# ProPrj_Attiny1616_Devboard_2024-11-25.net
KiCad netlist of a schematic drawn in EasyEDA Pro
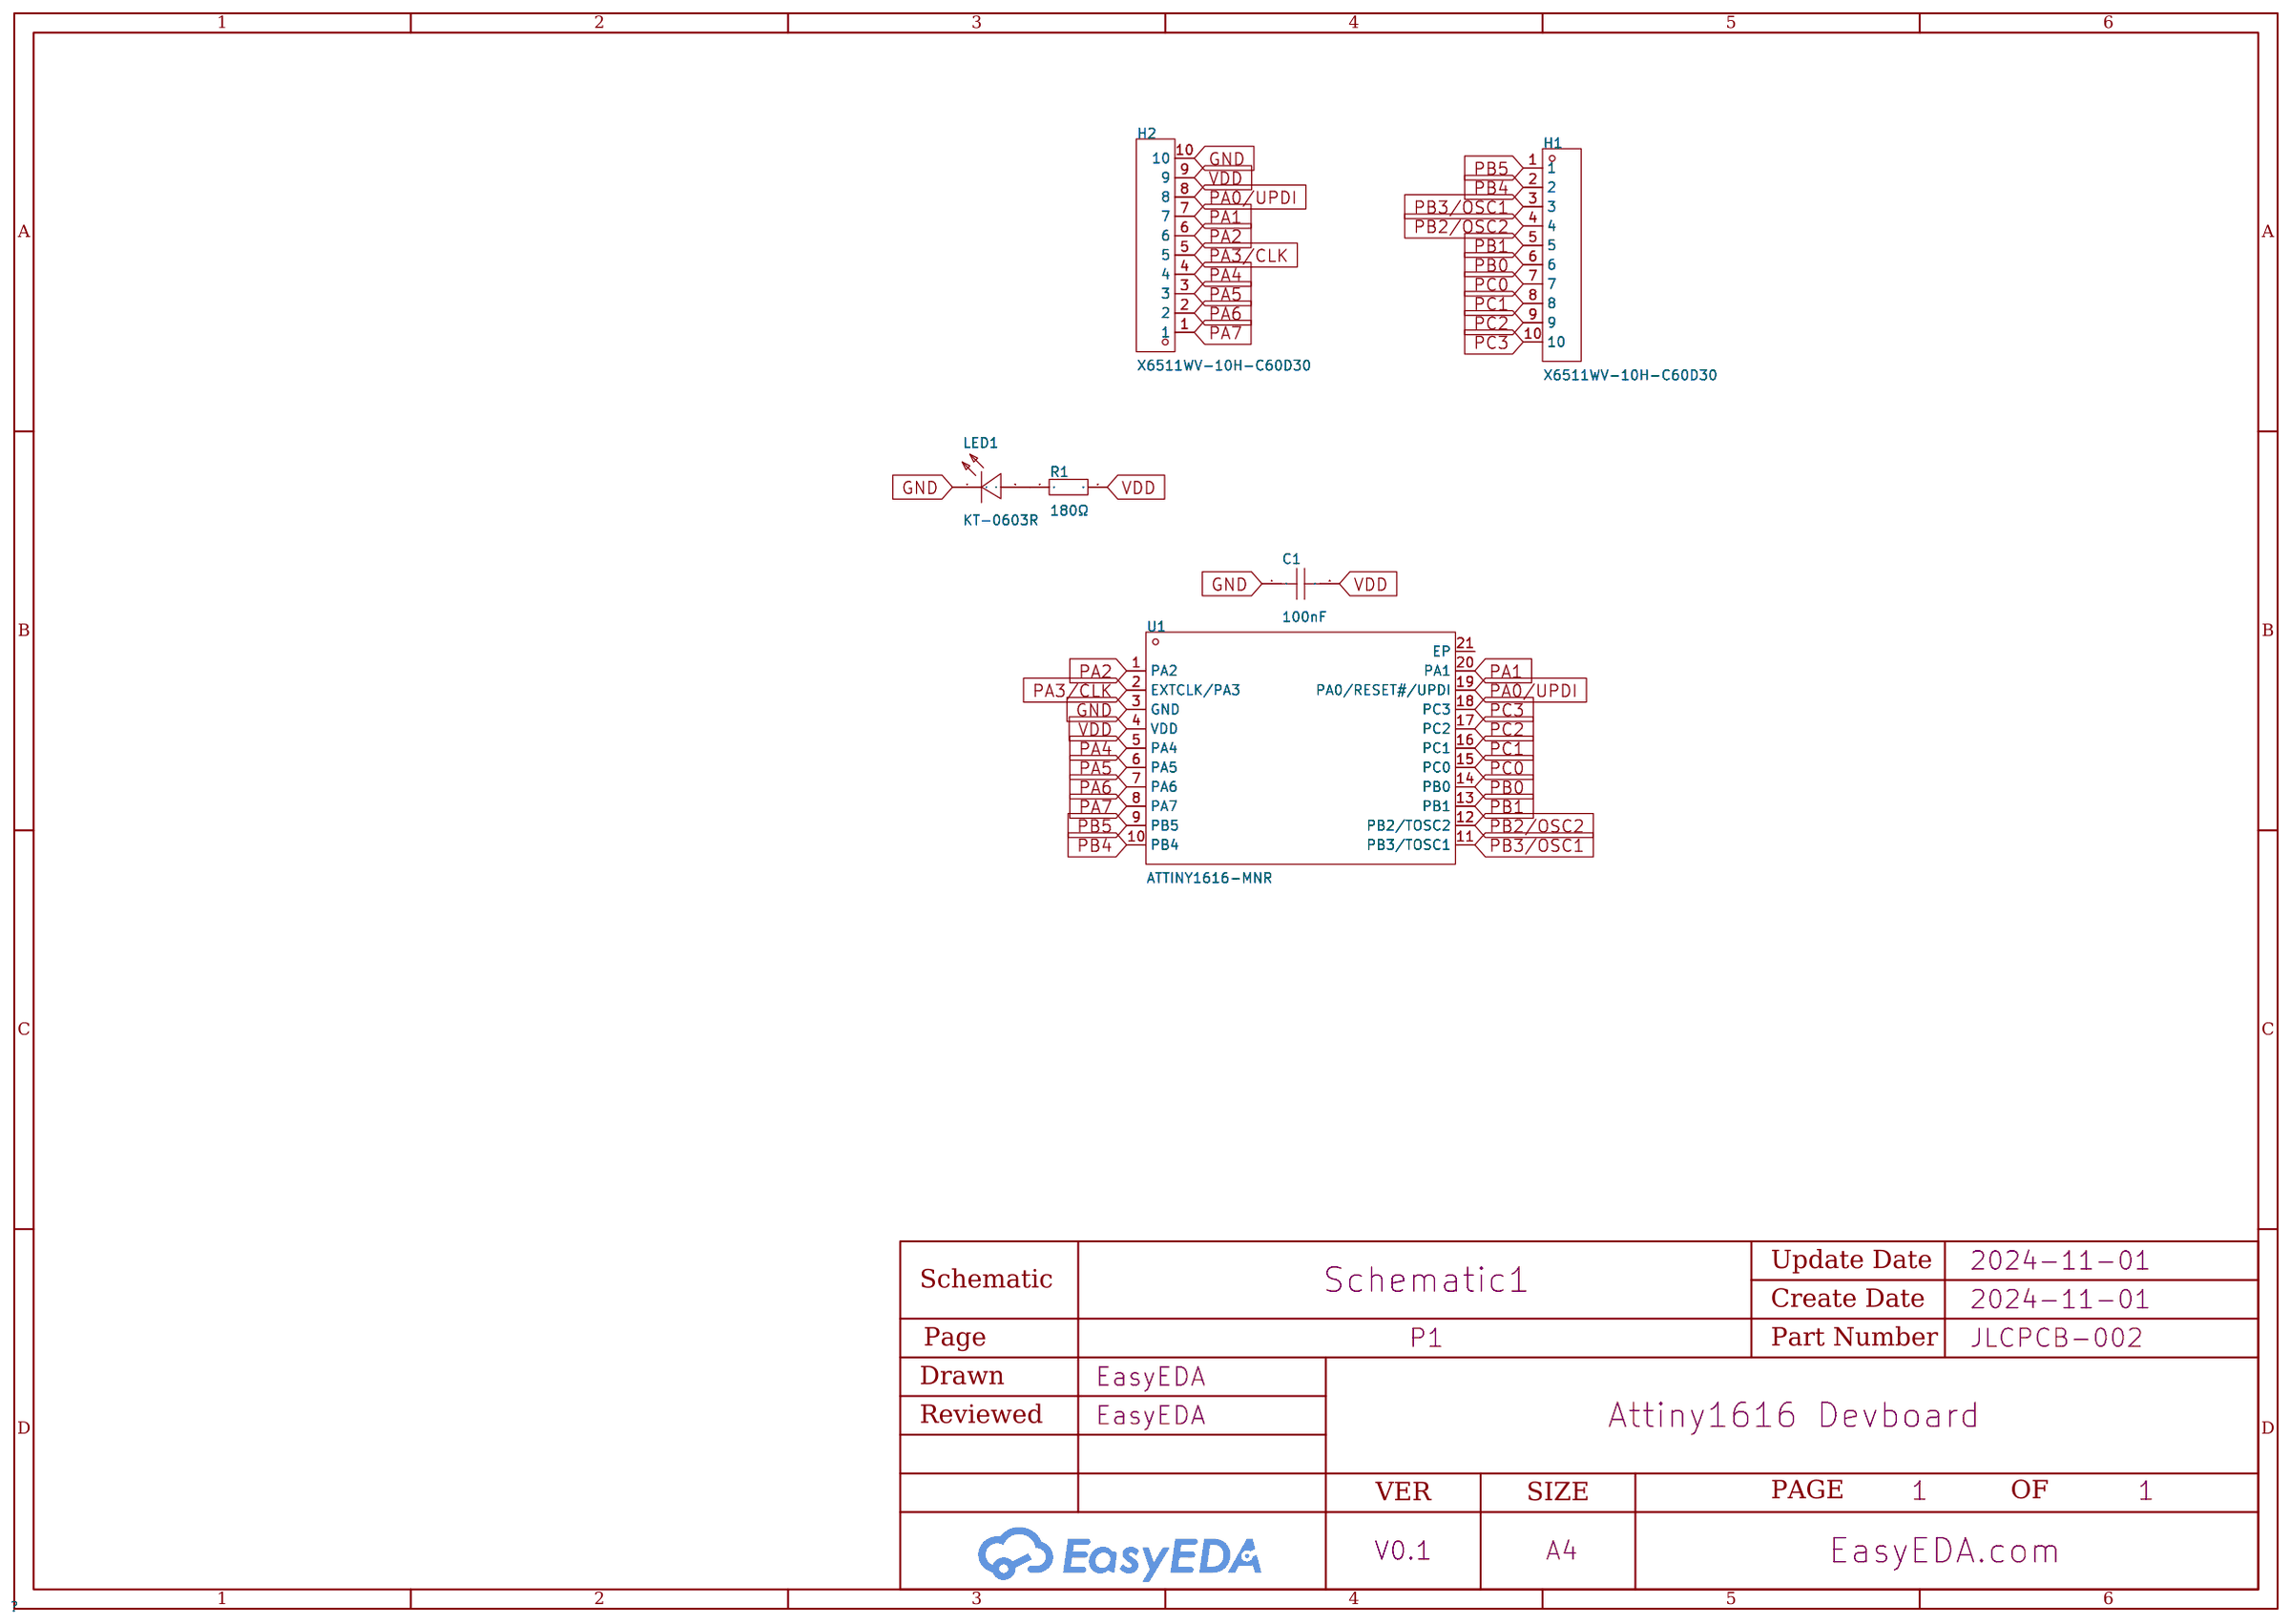
[diagram p0: schematic sheet]

(export (version "E")
  (design (tool "Eeschema 10.0.6"))
  (components
    (comp (ref "C1")
      (value "100nF")
      (footprint "easyedapro:C0402")
      (fields
        (field (name "Manufacturer Part") "CL05B104KO5NNNC")
        (field (name "Manufacturer") "SAMSUNG(三星)")
      )
      (libsource (lib "easyedapro") (part "CL05B104KO5NNNC"))
    )
    (comp (ref "H1")
      (value "X6511WV-10H-C60D30")
      (footprint "easyedapro:HDR-TH_10P-P2.54-V-M")
      (fields (field (name "Manufacturer") "XKB Connection(中国星坤)"))
      (libsource (lib "easyedapro") (part "X6511WV-10H-C30D60"))
    )
    (comp (ref "H2")
      (value "X6511WV-10H-C60D30")
      (footprint "easyedapro:HDR-TH_10P-P2.54-V-M")
      (fields (field (name "Manufacturer") "XKB Connection(中国星坤)"))
      (libsource (lib "easyedapro") (part "X6511WV-10H-C30D60"))
    )
    (comp (ref "LED1")
      (value "KT-0603R")
      (footprint "easyedapro:LED0603-RD")
      (fields (field (name "Manufacturer") "KENTO"))
      (libsource (lib "easyedapro") (part "KT-0603R"))
    )
    (comp (ref "R1")
      (value "180Ω")
      (footprint "easyedapro:R0603")
      (fields (field (name "Manufacturer Part") "RC0603FR-07180RL") (field (name "Manufacturer") "YAGEO(国巨)"))
      (libsource (lib "easyedapro") (part "RC0603FR-07180RL"))
    )
    (comp (ref "U1")
      (value "ATTINY1616-MNR")
      (footprint "easyedapro:QFN-20_L3.0-W3.0-P0.40-BL-EP1.7")
      (fields (field (name "Manufacturer") "MICROCHIP(美国微芯)"))
      (libsource (lib "easyedapro") (part "ATTINY1616-MNR"))
    )
  )
  (nets
    (net (code "1") (name "GND") (class "Default")
      (node (ref "C1") (pin "1") (pinfunction "1_1") (pintype "unspecified"))
      (node (ref "H2") (pin "10") (pinfunction "10_10") (pintype "unspecified"))
      (node (ref "LED1") (pin "1") (pinfunction "K_1") (pintype "unspecified"))
      (node (ref "U1") (pin "3") (pinfunction "GND_3") (pintype "input"))
    )
    (net (code "2") (name "Net-(LED1-A)") (class "Default")
      (node (ref "LED1") (pin "2") (pinfunction "A_2") (pintype "unspecified"))
      (node (ref "R1") (pin "1") (pinfunction "1_1") (pintype "input"))
    )
    (net (code "3") (name "PA0{slash}UPDI") (class "Default")
      (node (ref "H2") (pin "8") (pinfunction "8_8") (pintype "unspecified"))
      (node (ref "U1") (pin "19") (pinfunction "PA0/RESET#/UPDI_19") (pintype "input"))
    )
    (net (code "4") (name "PA1") (class "Default")
      (node (ref "H2") (pin "7") (pinfunction "7_7") (pintype "unspecified"))
      (node (ref "U1") (pin "20") (pinfunction "PA1_20") (pintype "input"))
    )
    (net (code "5") (name "PA2") (class "Default")
      (node (ref "H2") (pin "6") (pinfunction "6_6") (pintype "unspecified"))
      (node (ref "U1") (pin "1") (pinfunction "PA2_1") (pintype "input"))
    )
    (net (code "6") (name "PA3{slash}CLK") (class "Default")
      (node (ref "H2") (pin "5") (pinfunction "5_5") (pintype "unspecified"))
      (node (ref "U1") (pin "2") (pinfunction "EXTCLK/PA3_2") (pintype "input"))
    )
    (net (code "7") (name "PA4") (class "Default")
      (node (ref "H2") (pin "4") (pinfunction "4_4") (pintype "unspecified"))
      (node (ref "U1") (pin "5") (pinfunction "PA4_5") (pintype "input"))
    )
    (net (code "8") (name "PA5") (class "Default")
      (node (ref "H2") (pin "3") (pinfunction "3_3") (pintype "unspecified"))
      (node (ref "U1") (pin "6") (pinfunction "PA5_6") (pintype "input"))
    )
    (net (code "9") (name "PA6") (class "Default")
      (node (ref "H2") (pin "2") (pinfunction "2_2") (pintype "unspecified"))
      (node (ref "U1") (pin "7") (pinfunction "PA6_7") (pintype "input"))
    )
    (net (code "10") (name "PA7") (class "Default")
      (node (ref "H2") (pin "1") (pinfunction "1_1") (pintype "unspecified"))
      (node (ref "U1") (pin "8") (pinfunction "PA7_8") (pintype "input"))
    )
    (net (code "11") (name "PB0") (class "Default")
      (node (ref "H1") (pin "6") (pinfunction "6_6") (pintype "unspecified"))
      (node (ref "U1") (pin "14") (pinfunction "PB0_14") (pintype "input"))
    )
    (net (code "12") (name "PB1") (class "Default")
      (node (ref "H1") (pin "5") (pinfunction "5_5") (pintype "unspecified"))
      (node (ref "U1") (pin "13") (pinfunction "PB1_13") (pintype "input"))
    )
    (net (code "13") (name "PB2{slash}OSC2") (class "Default")
      (node (ref "H1") (pin "4") (pinfunction "4_4") (pintype "unspecified"))
      (node (ref "U1") (pin "12") (pinfunction "PB2/TOSC2_12") (pintype "input"))
    )
    (net (code "14") (name "PB3{slash}OSC1") (class "Default")
      (node (ref "H1") (pin "3") (pinfunction "3_3") (pintype "unspecified"))
      (node (ref "U1") (pin "11") (pinfunction "PB3/TOSC1_11") (pintype "input"))
    )
    (net (code "15") (name "PB4") (class "Default")
      (node (ref "H1") (pin "2") (pinfunction "2_2") (pintype "unspecified"))
      (node (ref "U1") (pin "10") (pinfunction "PB4_10") (pintype "input"))
    )
    (net (code "16") (name "PB5") (class "Default")
      (node (ref "H1") (pin "1") (pinfunction "1_1") (pintype "unspecified"))
      (node (ref "U1") (pin "9") (pinfunction "PB5_9") (pintype "input"))
    )
    (net (code "17") (name "PC0") (class "Default")
      (node (ref "H1") (pin "7") (pinfunction "7_7") (pintype "unspecified"))
      (node (ref "U1") (pin "15") (pinfunction "PC0_15") (pintype "input"))
    )
    (net (code "18") (name "PC1") (class "Default")
      (node (ref "H1") (pin "8") (pinfunction "8_8") (pintype "unspecified"))
      (node (ref "U1") (pin "16") (pinfunction "PC1_16") (pintype "input"))
    )
    (net (code "19") (name "PC2") (class "Default")
      (node (ref "H1") (pin "9") (pinfunction "9_9") (pintype "unspecified"))
      (node (ref "U1") (pin "17") (pinfunction "PC2_17") (pintype "input"))
    )
    (net (code "20") (name "PC3") (class "Default")
      (node (ref "H1") (pin "10") (pinfunction "10_10") (pintype "unspecified"))
      (node (ref "U1") (pin "18") (pinfunction "PC3_18") (pintype "input"))
    )
    (net (code "21") (name "VDD") (class "Default")
      (node (ref "C1") (pin "2") (pinfunction "2_2") (pintype "unspecified"))
      (node (ref "H2") (pin "9") (pinfunction "9_9") (pintype "unspecified"))
      (node (ref "R1") (pin "2") (pinfunction "2_2") (pintype "input"))
      (node (ref "U1") (pin "4") (pinfunction "VDD_4") (pintype "input"))
    )
    (net (code "22") (name "unconnected-(U1-EP-Pad21)") (class "Default")
      (node (ref "U1") (pin "21") (pinfunction "EP_21") (pintype "input"))
    )
  )
)
